# Schematic_Capstone.net
KiCad netlist of a schematic drawn in Altium Designer
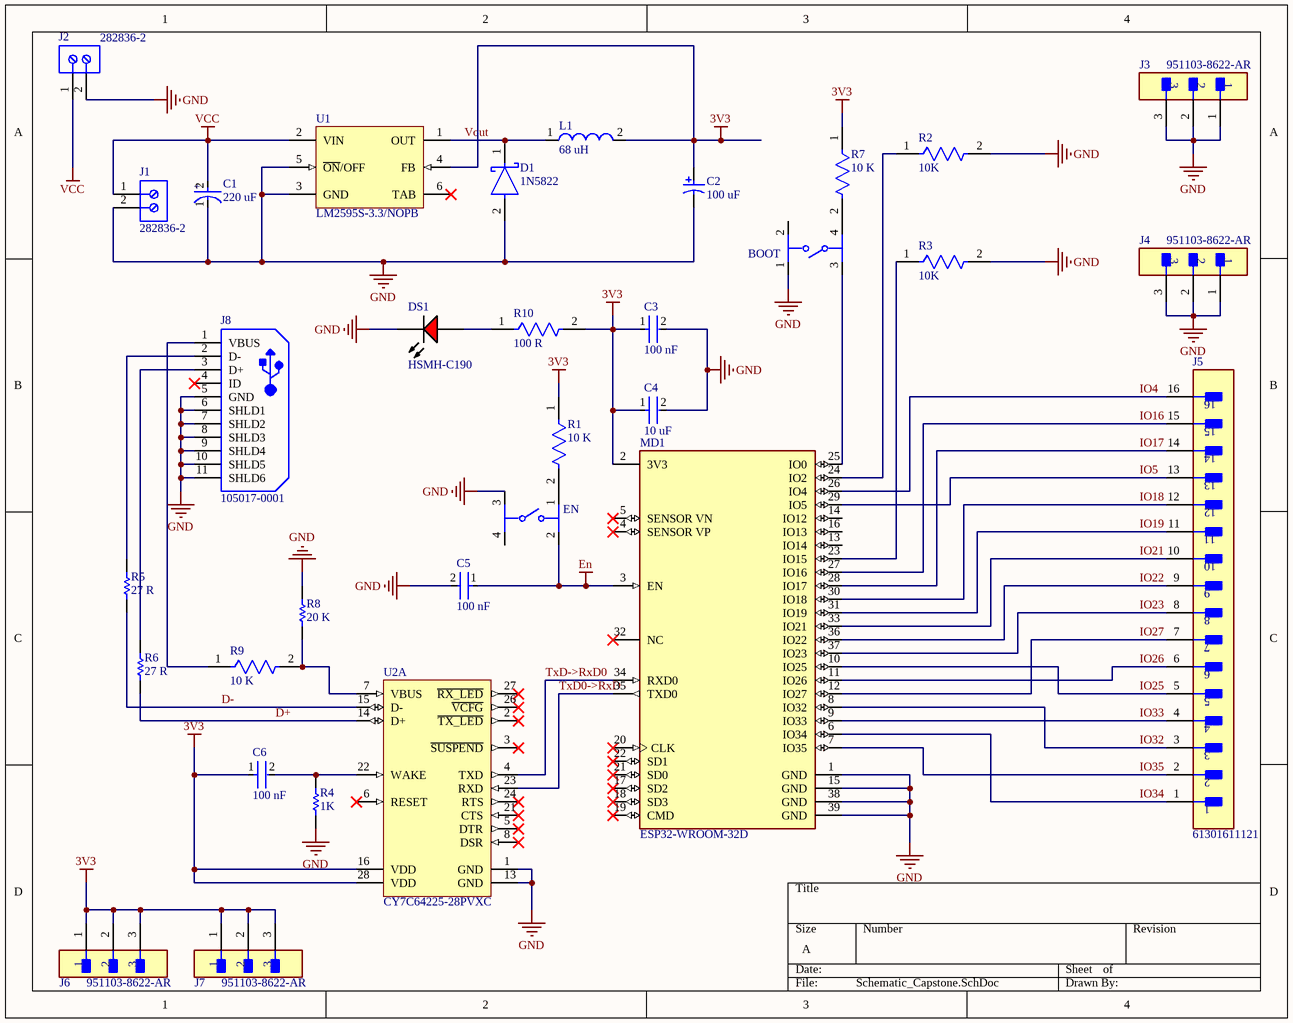
[diagram p0: Schematic_Capstone.SchDoc]

(export (version "E")
  (design (tool "Eeschema 10.0.6"))
  (components
    (comp (ref "BOOT")
      (value "PTS645SM43SMTR92LFS")
      (footprint "FP-PTS645SM43SMTR92LFS-MFG")
      (description "SWITCH TACTILE SPST-NO 0.05A 12V")
      (libsource (lib "Altium Content Vault") (part "1adf0dd01260c80cf25a44bfd6b99ba"))
    )
    (comp (ref "C1")
      (value "220 uF")
      (footprint "FP-860010473011-MFG")
      (description "CAP 220 UF 20% 25 V")
      (fields (field (name "TOLERANCE") "20%"))
      (libsource (lib "Altium Content Vault") (part "cf48714ba7e38822c1575c7ec0b6d1f"))
    )
    (comp (ref "C2")
      (value "100 uF")
      (footprint "VISH-7343-31_N")
      (fields (field (name "TOLERANCE") "1%"))
      (libsource (lib "Altium Content Vault") (part "CAP-P-2"))
    )
    (comp (ref "C3")
      (value "100 nF")
      (footprint "FP-C0805C-DN-MFG")
      (description "CAP CER 0.1UF 50V X7R 0805")
      (fields
        (field (name "MANUFACTURER PART NUMBER") "C0805C104K5RACTU")
        (field (name "MANUFACTURER") "KEMET")
      )
      (libsource (lib "Altium Content Vault") (part "b4654b650e69147ec39a6b967a45e02"))
    )
    (comp (ref "C4")
      (value "10 uF")
      (footprint "FP-C3225-250-0_45-MFG")
      (description "COMMERCIAL GRADE GENERAL PURPOSE")
      (libsource (lib "Altium Content Vault") (part "b4654b650e69147ec39a6b967a45e02"))
    )
    (comp (ref "C5")
      (value "100 nF")
      (footprint "FP-C0805C-DN-MFG")
      (description "CAP CER 0.1UF 50V X7R 0805")
      (fields
        (field (name "MANUFACTURER PART NUMBER") "C0805C104K5RACTU")
        (field (name "MANUFACTURER") "KEMET")
      )
      (libsource (lib "Altium Content Vault") (part "b4654b650e69147ec39a6b967a45e02"))
    )
    (comp (ref "C6")
      (value "100 nF")
      (footprint "FP-C0805C-DN-MFG")
      (description "CAP CER 0.1UF 50V X7R 0805")
      (fields
        (field (name "MANUFACTURER PART NUMBER") "C0805C104K5RACTU")
        (field (name "MANUFACTURER") "KEMET")
      )
      (libsource (lib "Altium Content Vault") (part "b4654b650e69147ec39a6b967a45e02"))
    )
    (comp (ref "D1")
      (value "1N5822")
      (footprint "FP-DO-201AD-MFG")
      (description "DIODE SCHOTTKY 40V 3A DO201AD")
      (fields
        (field (name "OCTOPART") "https://octopart.com/1n5822-stmicroelectronics-323225")
        (field (name "MANUFACTURER") "STMicroelectronics")
      )
      (libsource (lib "Altium Content Vault") (part "1d6ec82d83fb6aee721767c19dac4b9"))
    )
    (comp (ref "DS1")
      (value "HSMH-C190")
      (footprint "AVAG-HSMX-C190_V")
      (description "LED Uni-Color Red, 65 mW, 20 mA, -40 to 85 degC, 2-Pin SMD, RoHS, Tape and Reel")
      (libsource (lib "Altium Content Vault") (part "LED-RED-AK-2"))
    )
    (comp (ref "EN")
      (value "PTS645SM43SMTR92LFS")
      (footprint "FP-PTS645SM43SMTR92LFS-MFG")
      (description "SWITCH TACTILE SPST-NO 0.05A 12V")
      (libsource (lib "Altium Content Vault") (part "1adf0dd01260c80cf25a44bfd6b99ba"))
    )
    (comp (ref "J1")
      (value "282836-2")
      (footprint "TECO-282836-2_V")
      (description "Female Header, Pitch 5 mm, 1 x 2 Position, Height 10 mm, Tail Length 3.5 mm, Rohs, Bulk")
      (fields (field (name "VOLTAGE") "300V") (field (name "MANUFACTURER") "TE Connectivity"))
      (libsource (lib "Altium Content Vault") (part "CN-1P-F-TB2"))
    )
    (comp (ref "J2")
      (value "282836-2")
      (footprint "TECO-282836-2_V")
      (description "Female Header, Pitch 5 mm, 1 x 2 Position, Height 10 mm, Tail Length 3.5 mm, Rohs, Bulk")
      (fields (field (name "VOLTAGE") "300V") (field (name "MANUFACTURER") "TE Connectivity"))
      (libsource (lib "Altium Content Vault") (part "CN-1P-F-TB2"))
    )
    (comp (ref "J3")
      (value "951103-8622-AR")
      (footprint "FP-951103-8622-AR-MFG")
      (description "CONN HEADER VERT 3POS 2MM")
      (fields
        (field (name "OCTOPART") "https://octopart.com/951103-8622-ar-3m-14400669")
        (field (name "MANUFACTURER") "3M")
      )
      (libsource (lib "") (part "0d3f023dd272f625e17a2be33dea85f_1"))
    )
    (comp (ref "J4")
      (value "951103-8622-AR")
      (footprint "FP-951103-8622-AR-MFG")
      (description "CONN HEADER VERT 3POS 2MM")
      (fields
        (field (name "OCTOPART") "https://octopart.com/951103-8622-ar-3m-14400669")
        (field (name "MANUFACTURER") "3M")
      )
      (libsource (lib "") (part "0d3f023dd272f625e17a2be33dea85f_1"))
    )
    (comp (ref "J5")
      (value "61301611121")
      (footprint "FP-61301611121-MFG")
      (description "CONN HEADER VERT 16POS 2.54MM")
      (libsource (lib "Altium Content Vault") (part "e5c9d856941f54a8fdb498ab6b27a18"))
    )
    (comp (ref "J6")
      (value "951103-8622-AR")
      (footprint "FP-951103-8622-AR-MFG")
      (description "CONN HEADER VERT 3POS 2MM")
      (fields
        (field (name "OCTOPART") "https://octopart.com/951103-8622-ar-3m-14400669")
        (field (name "MANUFACTURER") "3M")
      )
      (libsource (lib "Altium Content Vault") (part "0d3f023dd272f625e17a2be33dea85f"))
    )
    (comp (ref "J7")
      (value "951103-8622-AR")
      (footprint "FP-951103-8622-AR-MFG")
      (description "CONN HEADER VERT 3POS 2MM")
      (fields
        (field (name "OCTOPART") "https://octopart.com/951103-8622-ar-3m-14400669")
        (field (name "MANUFACTURER") "3M")
      )
      (libsource (lib "Altium Content Vault") (part "0d3f023dd272f625e17a2be33dea85f"))
    )
    (comp (ref "J8")
      (value "105017-0001")
      (footprint "USB-MICRO-B_V")
      (fields (field (name "MANUFACTURER") "Molex"))
      (libsource (lib "Altium Content Vault") (part "USB-5-6SHLD"))
    )
    (comp (ref "L1")
      (value "68 uH")
      (footprint "WE-PD-L")
      (description "SMD-Shielded Power Inductor WE-PD, L = 68.0 µH")
      (libsource (lib "Altium Content Vault") (part "PAS-IND-INDUCTOR-2"))
    )
    (comp (ref "MD1")
      (value "ESP32-WROOM-32D")
      (footprint "FP-ESP32-WROOM-32D-MFG")
      (description "WIFI MODULE 32MBITS SPI FLASH")
      (fields
        (field (name "OCTOPART") "https://octopart.com/esp32-wroom-32d-espressif+systems-91040050")
        (field (name "MANUFACTURER") "Espressif Systems")
      )
      (libsource (lib "Altium Content Vault") (part "a031a76f8c27026a7a7f4657ff233a3"))
    )
    (comp (ref "R1")
      (value "10 K")
      (footprint "FP-CRCW2010-e3-IPC_B")
      (description "RES Thick Film, 10kΩ, 1%, 0.75W, 100ppm/°C, 2010")
      (fields (field (name "TOLERANCE") "1%"))
      (libsource (lib "Altium Content Vault") (part "1029c3af85768c4190bb7ad29bc67b5"))
    )
    (comp (ref "R2")
      (value "10K")
      (footprint "FP-CRCW2010-e3-IPC_B")
      (description "RES Thick Film, 10kΩ, 1%, 0.75W, 100ppm/°C, 2010")
      (fields (field (name "TOLERANCE") "1%"))
      (libsource (lib "Altium Content Vault") (part "1029c3af85768c4190bb7ad29bc67b5"))
    )
    (comp (ref "R3")
      (value "10K")
      (footprint "FP-CRCW2010-e3-IPC_B")
      (description "RES Thick Film, 10kΩ, 1%, 0.75W, 100ppm/°C, 2010")
      (fields (field (name "TOLERANCE") "1%"))
      (libsource (lib "Altium Content Vault") (part "1029c3af85768c4190bb7ad29bc67b5"))
    )
    (comp (ref "R4")
      (value "1K")
      (footprint "RESC1005X40X25NL05T05")
      (fields (field (name "MANUFACTURER") "Panasonic") (field (name "PART NUMBER") "ERJ-2GEJ102X"))
      (libsource (lib "Altium Content Vault") (part "RES"))
    )
    (comp (ref "R5")
      (value "27 R")
      (footprint "RESC3216X70X50NL05T20")
      (fields (field (name "MANUFACTURER") "Panasonic") (field (name "PART NUMBER") "ERJ8ENF27R0V"))
      (libsource (lib "Altium Content Vault") (part "RES"))
    )
    (comp (ref "R6")
      (value "27 R")
      (footprint "RESC3216X70X50NL05T20")
      (fields (field (name "MANUFACTURER") "Panasonic") (field (name "PART NUMBER") "ERJ8ENF27R0V"))
      (libsource (lib "Altium Content Vault") (part "RES"))
    )
    (comp (ref "R7")
      (value "10 K")
      (footprint "FP-CRCW2010-e3-IPC_B")
      (description "RES Thick Film, 10kΩ, 1%, 0.75W, 100ppm/°C, 2010")
      (fields (field (name "TOLERANCE") "1%"))
      (libsource (lib "Altium Content Vault") (part "1029c3af85768c4190bb7ad29bc67b5"))
    )
    (comp (ref "R8")
      (value "20 K")
      (footprint "RESC1608X55X25ML10T15")
      (fields (field (name "PART NUMBER") "RC0603FR-1020KL") (field (name "MANUFACTURER") "Yageo"))
      (libsource (lib "Altium Content Vault") (part "RES"))
    )
    (comp (ref "R9")
      (value "10 K")
      (footprint "FP-CRCW2010-e3-IPC_B")
      (description "RES Thick Film, 10kΩ, 1%, 0.75W, 100ppm/°C, 2010")
      (fields (field (name "TOLERANCE") "1%"))
      (libsource (lib "Altium Content Vault") (part "1029c3af85768c4190bb7ad29bc67b5"))
    )
    (comp (ref "R10")
      (value "100 R")
      (footprint "FP-CRCW0402-e3-IPC_C")
      (description "RES Thick Film, 100Ω, 1%, 0.063W, 100ppm/°C, 0402")
      (fields (field (name "TOLERANCE") "1%"))
      (libsource (lib "Altium Content Vault") (part "1029c3af85768c4190bb7ad29bc67b5"))
    )
    (comp (ref "U1")
      (value "LM2595S-3.3/NOPB")
      (footprint "KTT0005B_N")
      (description "SIMPLE SWITCHER® Power Converter 150 KHz 1A Step-Down Voltage Regulator, 5-pin TO-263, Pb-Free")
      (fields (field (name "MANUFACTURER") "Texas Instruments"))
      (libsource (lib "Altium Content Vault") (part "PM-REG-LM2595S-12"))
    )
    (comp (ref "U2")
      (value "CY7C64225-28PVXC")
      (footprint "CYP-PVX28_L")
      (description "USB-to-UART Bridge Controller, 3 to 5.25 V, 0 to 70 degC, 28-Pin SSOP (PVX28), Tube")
      (fields (field (name "MANUFACTURER") "Cypress"))
      (libsource (lib "Altium Content Vault") (part "CYP-CY7C6422-PV28"))
    )
  )
  (nets
    (net (code "1") (name "/D+") (class "Default")
      (node (ref "R6") (pin "1") (pinfunction "1_1") (pintype "passive"))
      (node (ref "U2") (pin "14") (pinfunction "D+_14") (pintype "bidirectional"))
    )
    (net (code "2") (name "/D-") (class "Default")
      (node (ref "R5") (pin "2") (pinfunction "2_2") (pintype "passive"))
      (node (ref "U2") (pin "15") (pinfunction "D-_15") (pintype "bidirectional"))
    )
    (net (code "3") (name "/IO4") (class "Default")
      (node (ref "J5") (pin "16") (pinfunction "16_16") (pintype "passive"))
      (node (ref "MD1") (pin "26") (pinfunction "IO4_26") (pintype "bidirectional"))
    )
    (net (code "4") (name "/IO5") (class "Default")
      (node (ref "J5") (pin "13") (pinfunction "13_13") (pintype "passive"))
      (node (ref "MD1") (pin "29") (pinfunction "IO5_29") (pintype "bidirectional"))
    )
    (net (code "5") (name "/IO16") (class "Default")
      (node (ref "J5") (pin "15") (pinfunction "15_15") (pintype "passive"))
      (node (ref "MD1") (pin "27") (pinfunction "IO16_27") (pintype "bidirectional"))
    )
    (net (code "6") (name "/IO17") (class "Default")
      (node (ref "J5") (pin "14") (pinfunction "14_14") (pintype "passive"))
      (node (ref "MD1") (pin "28") (pinfunction "IO17_28") (pintype "bidirectional"))
    )
    (net (code "7") (name "/IO18") (class "Default")
      (node (ref "J5") (pin "12") (pinfunction "12_12") (pintype "passive"))
      (node (ref "MD1") (pin "30") (pinfunction "IO18_30") (pintype "bidirectional"))
    )
    (net (code "8") (name "/IO19") (class "Default")
      (node (ref "J5") (pin "11") (pinfunction "11_11") (pintype "passive"))
      (node (ref "MD1") (pin "31") (pinfunction "IO19_31") (pintype "bidirectional"))
    )
    (net (code "9") (name "/IO21") (class "Default")
      (node (ref "J5") (pin "10") (pinfunction "10_10") (pintype "passive"))
      (node (ref "MD1") (pin "33") (pinfunction "IO21_33") (pintype "bidirectional"))
    )
    (net (code "10") (name "/IO22") (class "Default")
      (node (ref "J5") (pin "9") (pinfunction "9_9") (pintype "passive"))
      (node (ref "MD1") (pin "36") (pinfunction "IO22_36") (pintype "bidirectional"))
    )
    (net (code "11") (name "/IO23") (class "Default")
      (node (ref "J5") (pin "8") (pinfunction "8_8") (pintype "passive"))
      (node (ref "MD1") (pin "37") (pinfunction "IO23_37") (pintype "bidirectional"))
    )
    (net (code "12") (name "/IO25") (class "Default")
      (node (ref "J5") (pin "5") (pinfunction "5_5") (pintype "passive"))
      (node (ref "MD1") (pin "10") (pinfunction "IO25_10") (pintype "bidirectional"))
    )
    (net (code "13") (name "/IO26") (class "Default")
      (node (ref "J5") (pin "6") (pinfunction "6_6") (pintype "passive"))
      (node (ref "MD1") (pin "11") (pinfunction "IO26_11") (pintype "bidirectional"))
    )
    (net (code "14") (name "/IO27") (class "Default")
      (node (ref "J5") (pin "7") (pinfunction "7_7") (pintype "passive"))
      (node (ref "MD1") (pin "12") (pinfunction "IO27_12") (pintype "bidirectional"))
    )
    (net (code "15") (name "/IO32") (class "Default")
      (node (ref "J5") (pin "3") (pinfunction "3_3") (pintype "passive"))
      (node (ref "MD1") (pin "8") (pinfunction "IO32_8") (pintype "bidirectional"))
    )
    (net (code "16") (name "/IO33") (class "Default")
      (node (ref "J5") (pin "4") (pinfunction "4_4") (pintype "passive"))
      (node (ref "MD1") (pin "9") (pinfunction "IO33_9") (pintype "bidirectional"))
    )
    (net (code "17") (name "/IO34") (class "Default")
      (node (ref "J5") (pin "1") (pinfunction "1_1") (pintype "passive"))
      (node (ref "MD1") (pin "6") (pinfunction "IO34_6") (pintype "bidirectional"))
    )
    (net (code "18") (name "/IO35") (class "Default")
      (node (ref "J5") (pin "2") (pinfunction "2_2") (pintype "passive"))
      (node (ref "MD1") (pin "7") (pinfunction "IO35_7") (pintype "bidirectional"))
    )
    (net (code "19") (name "/TxD->RxD0") (class "Default")
      (node (ref "MD1") (pin "34") (pinfunction "RXD0_34") (pintype "input"))
      (node (ref "U2") (pin "4") (pinfunction "TXD_4") (pintype "output"))
    )
    (net (code "20") (name "/TxD0->RxD") (class "Default")
      (node (ref "MD1") (pin "35") (pinfunction "TXD0_35") (pintype "output"))
      (node (ref "U2") (pin "23") (pinfunction "RXD_23") (pintype "input"))
    )
    (net (code "21") (name "/Vout") (class "Default")
      (node (ref "D1") (pin "1") (pinfunction "C_1") (pintype "passive"))
      (node (ref "L1") (pin "1") (pinfunction "1_1") (pintype "passive"))
      (node (ref "U1") (pin "1") (pinfunction "OUT_1") (pintype "power_in"))
    )
    (net (code "22") (name "3V3") (class "Default")
      (node (ref "C2") (pin "1") (pinfunction "1_1") (pintype "passive"))
      (node (ref "C3") (pin "1") (pinfunction "1_1") (pintype "passive"))
      (node (ref "C4") (pin "1") (pinfunction "1_1") (pintype "passive"))
      (node (ref "C6") (pin "1") (pinfunction "1_1") (pintype "passive"))
      (node (ref "J6") (pin "1") (pinfunction "1_1") (pintype "passive"))
      (node (ref "J6") (pin "2") (pinfunction "2_2") (pintype "passive"))
      (node (ref "J6") (pin "3") (pinfunction "3_3") (pintype "passive"))
      (node (ref "J7") (pin "1") (pinfunction "1_1") (pintype "passive"))
      (node (ref "J7") (pin "2") (pinfunction "2_2") (pintype "passive"))
      (node (ref "J7") (pin "3") (pinfunction "3_3") (pintype "passive"))
      (node (ref "L1") (pin "2") (pinfunction "2_2") (pintype "passive"))
      (node (ref "MD1") (pin "2") (pinfunction "3V3_2") (pintype "power_in"))
      (node (ref "R1") (pin "1") (pinfunction "1_1") (pintype "passive"))
      (node (ref "R10") (pin "2") (pinfunction "2_2") (pintype "passive"))
      (node (ref "R7") (pin "1") (pinfunction "1_1") (pintype "passive"))
      (node (ref "U1") (pin "4") (pinfunction "FB_4") (pintype "input"))
      (node (ref "U2") (pin "16") (pinfunction "VDD_16") (pintype "power_in"))
      (node (ref "U2") (pin "28") (pinfunction "VDD_28") (pintype "power_in"))
    )
    (net (code "23") (name "En") (class "Default")
      (node (ref "C5") (pin "1") (pinfunction "1_1") (pintype "passive"))
      (node (ref "EN") (pin "2") (pinfunction "2_2") (pintype "passive"))
      (node (ref "MD1") (pin "3") (pinfunction "EN_3") (pintype "input"))
    )
    (net (code "24") (name "GND") (class "Default")
      (node (ref "BOOT") (pin "1") (pinfunction "1_1") (pintype "passive"))
      (node (ref "C1") (pin "1") (pinfunction "C_1") (pintype "passive"))
      (node (ref "C2") (pin "2") (pinfunction "2_2") (pintype "passive"))
      (node (ref "C3") (pin "2") (pinfunction "2_2") (pintype "passive"))
      (node (ref "C4") (pin "2") (pinfunction "2_2") (pintype "passive"))
      (node (ref "C5") (pin "2") (pinfunction "2_2") (pintype "passive"))
      (node (ref "D1") (pin "2") (pinfunction "A_2") (pintype "passive"))
      (node (ref "DS1") (pin "2") (pinfunction "K_2") (pintype "passive"))
      (node (ref "EN") (pin "3") (pinfunction "3_3") (pintype "passive"))
      (node (ref "J1") (pin "2") (pinfunction "2_2") (pintype "passive"))
      (node (ref "J2") (pin "2") (pinfunction "2_2") (pintype "passive"))
      (node (ref "J3") (pin "1") (pinfunction "1_1") (pintype "passive"))
      (node (ref "J3") (pin "2") (pinfunction "2_2") (pintype "passive"))
      (node (ref "J3") (pin "3") (pinfunction "3_3") (pintype "passive"))
      (node (ref "J4") (pin "1") (pinfunction "1_1") (pintype "passive"))
      (node (ref "J4") (pin "2") (pinfunction "2_2") (pintype "passive"))
      (node (ref "J4") (pin "3") (pinfunction "3_3") (pintype "passive"))
      (node (ref "J8") (pin "10") (pinfunction "SHLD5_10") (pintype "passive"))
      (node (ref "J8") (pin "11") (pinfunction "SHLD6_11") (pintype "passive"))
      (node (ref "J8") (pin "5") (pinfunction "GND_5") (pintype "passive"))
      (node (ref "J8") (pin "6") (pinfunction "SHLD1_6") (pintype "passive"))
      (node (ref "J8") (pin "7") (pinfunction "SHLD2_7") (pintype "passive"))
      (node (ref "J8") (pin "8") (pinfunction "SHLD3_8") (pintype "passive"))
      (node (ref "J8") (pin "9") (pinfunction "SHLD4_9") (pintype "passive"))
      (node (ref "MD1") (pin "1") (pinfunction "GND_1") (pintype "power_in"))
      (node (ref "MD1") (pin "15") (pinfunction "GND_15") (pintype "power_in"))
      (node (ref "MD1") (pin "38") (pinfunction "GND_38") (pintype "power_in"))
      (node (ref "MD1") (pin "39") (pinfunction "GND_39") (pintype "power_in"))
      (node (ref "R2") (pin "2") (pinfunction "2_2") (pintype "passive"))
      (node (ref "R3") (pin "2") (pinfunction "2_2") (pintype "passive"))
      (node (ref "R4") (pin "2") (pinfunction "2_2") (pintype "passive"))
      (node (ref "R8") (pin "2") (pinfunction "2_2") (pintype "passive"))
      (node (ref "U1") (pin "3") (pinfunction "GND_3") (pintype "power_in"))
      (node (ref "U1") (pin "5") (pinfunction "~{ON}/OFF_5") (pintype "input"))
      (node (ref "U2") (pin "1") (pinfunction "GND_1") (pintype "power_in"))
      (node (ref "U2") (pin "13") (pinfunction "GND_13") (pintype "power_in"))
    )
    (net (code "25") (name "Net-(BOOT-Pad4)") (class "Default")
      (node (ref "BOOT") (pin "4") (pinfunction "4_4") (pintype "passive"))
      (node (ref "R7") (pin "2") (pinfunction "2_2") (pintype "passive"))
    )
    (net (code "26") (name "Net-(DS1-A)") (class "Default")
      (node (ref "DS1") (pin "1") (pinfunction "A_1") (pintype "passive"))
      (node (ref "R10") (pin "1") (pinfunction "1_1") (pintype "passive"))
    )
    (net (code "27") (name "Net-(EN-Pad1)") (class "Default")
      (node (ref "EN") (pin "1") (pinfunction "1_1") (pintype "passive"))
      (node (ref "R1") (pin "2") (pinfunction "2_2") (pintype "passive"))
    )
    (net (code "28") (name "Net-(J8-D+)") (class "Default")
      (node (ref "J8") (pin "3") (pinfunction "D+_3") (pintype "passive"))
      (node (ref "R6") (pin "2") (pinfunction "2_2") (pintype "passive"))
    )
    (net (code "29") (name "Net-(J8-D-)") (class "Default")
      (node (ref "J8") (pin "2") (pinfunction "D-_2") (pintype "passive"))
      (node (ref "R5") (pin "1") (pinfunction "1_1") (pintype "passive"))
    )
    (net (code "30") (name "Net-(J8-VBUS)") (class "Default")
      (node (ref "J8") (pin "1") (pinfunction "VBUS_1") (pintype "passive"))
      (node (ref "R9") (pin "1") (pinfunction "1_1") (pintype "passive"))
    )
    (net (code "31") (name "Net-(MD1-IO0)") (class "Default")
      (node (ref "BOOT") (pin "3") (pinfunction "3_3") (pintype "passive"))
      (node (ref "MD1") (pin "25") (pinfunction "IO0_25") (pintype "bidirectional"))
    )
    (net (code "32") (name "Net-(MD1-IO2)") (class "Default")
      (node (ref "MD1") (pin "24") (pinfunction "IO2_24") (pintype "bidirectional"))
      (node (ref "R2") (pin "1") (pinfunction "1_1") (pintype "passive"))
    )
    (net (code "33") (name "Net-(MD1-IO15)") (class "Default")
      (node (ref "MD1") (pin "23") (pinfunction "IO15_23") (pintype "bidirectional"))
      (node (ref "R3") (pin "1") (pinfunction "1_1") (pintype "passive"))
    )
    (net (code "34") (name "Net-(U2A-VBUS)") (class "Default")
      (node (ref "R8") (pin "1") (pinfunction "1_1") (pintype "passive"))
      (node (ref "R9") (pin "2") (pinfunction "2_2") (pintype "passive"))
      (node (ref "U2") (pin "7") (pinfunction "VBUS_7") (pintype "input"))
    )
    (net (code "35") (name "Net-(U2A-WAKE)") (class "Default")
      (node (ref "C6") (pin "2") (pinfunction "2_2") (pintype "passive"))
      (node (ref "R4") (pin "1") (pinfunction "1_1") (pintype "passive"))
      (node (ref "U2") (pin "22") (pinfunction "WAKE_22") (pintype "input"))
    )
    (net (code "36") (name "VCC") (class "Default")
      (node (ref "C1") (pin "2") (pinfunction "A_2") (pintype "passive"))
      (node (ref "J1") (pin "1") (pinfunction "1_1") (pintype "passive"))
      (node (ref "J2") (pin "1") (pinfunction "1_1") (pintype "passive"))
      (node (ref "U1") (pin "2") (pinfunction "VIN_2") (pintype "power_in"))
    )
    (net (code "37") (name "unconnected-(BOOT-Pad2)") (class "Default")
      (node (ref "BOOT") (pin "2") (pinfunction "2_2") (pintype "passive"))
    )
    (net (code "38") (name "unconnected-(EN-Pad4)") (class "Default")
      (node (ref "EN") (pin "4") (pinfunction "4_4") (pintype "passive"))
    )
    (net (code "39") (name "unconnected-(J8-ID-Pad4)") (class "Default")
      (node (ref "J8") (pin "4") (pinfunction "ID_4") (pintype "passive+no_connect"))
    )
    (net (code "40") (name "unconnected-(MD1-CLK-Pad20)") (class "Default")
      (node (ref "MD1") (pin "20") (pinfunction "CLK_20") (pintype "input+no_connect"))
    )
    (net (code "41") (name "unconnected-(MD1-CMD-Pad19)") (class "Default")
      (node (ref "MD1") (pin "19") (pinfunction "CMD_19") (pintype "bidirectional+no_connect"))
    )
    (net (code "42") (name "unconnected-(MD1-IO12-Pad14)") (class "Default")
      (node (ref "MD1") (pin "14") (pinfunction "IO12_14") (pintype "bidirectional"))
    )
    (net (code "43") (name "unconnected-(MD1-IO13-Pad16)") (class "Default")
      (node (ref "MD1") (pin "16") (pinfunction "IO13_16") (pintype "bidirectional"))
    )
    (net (code "44") (name "unconnected-(MD1-IO14-Pad13)") (class "Default")
      (node (ref "MD1") (pin "13") (pinfunction "IO14_13") (pintype "bidirectional"))
    )
    (net (code "45") (name "unconnected-(MD1-NC-Pad32)") (class "Default")
      (node (ref "MD1") (pin "32") (pinfunction "NC_32") (pintype "passive+no_connect"))
    )
    (net (code "46") (name "unconnected-(MD1-SD0-Pad21)") (class "Default")
      (node (ref "MD1") (pin "21") (pinfunction "SD0_21") (pintype "bidirectional+no_connect"))
    )
    (net (code "47") (name "unconnected-(MD1-SD1-Pad22)") (class "Default")
      (node (ref "MD1") (pin "22") (pinfunction "SD1_22") (pintype "bidirectional+no_connect"))
    )
    (net (code "48") (name "unconnected-(MD1-SD2-Pad17)") (class "Default")
      (node (ref "MD1") (pin "17") (pinfunction "SD2_17") (pintype "bidirectional+no_connect"))
    )
    (net (code "49") (name "unconnected-(MD1-SD3-Pad18)") (class "Default")
      (node (ref "MD1") (pin "18") (pinfunction "SD3_18") (pintype "bidirectional+no_connect"))
    )
    (net (code "50") (name "unconnected-(MD1-SENSOR_VN-Pad5)") (class "Default")
      (node (ref "MD1") (pin "5") (pinfunction "SENSOR_VN_5") (pintype "bidirectional+no_connect"))
    )
    (net (code "51") (name "unconnected-(MD1-SENSOR_VP-Pad4)") (class "Default")
      (node (ref "MD1") (pin "4") (pinfunction "SENSOR_VP_4") (pintype "bidirectional+no_connect"))
    )
    (net (code "52") (name "unconnected-(U1-TAB-Pad6)") (class "Default")
      (node (ref "U1") (pin "6") (pinfunction "TAB_6") (pintype "power_in+no_connect"))
    )
    (net (code "53") (name "unconnected-(U2A-CTS-Pad21)") (class "Default")
      (node (ref "U2") (pin "21") (pinfunction "CTS_21") (pintype "input+no_connect"))
    )
    (net (code "54") (name "unconnected-(U2A-DSR-Pad8)") (class "Default")
      (node (ref "U2") (pin "8") (pinfunction "DSR_8") (pintype "input+no_connect"))
    )
    (net (code "55") (name "unconnected-(U2A-DTR-Pad5)") (class "Default")
      (node (ref "U2") (pin "5") (pinfunction "DTR_5") (pintype "output+no_connect"))
    )
    (net (code "56") (name "unconnected-(U2A-RESET-Pad6)") (class "Default")
      (node (ref "U2") (pin "6") (pinfunction "RESET_6") (pintype "input+no_connect"))
    )
    (net (code "57") (name "unconnected-(U2A-RTS-Pad24)") (class "Default")
      (node (ref "U2") (pin "24") (pinfunction "RTS_24") (pintype "output+no_connect"))
    )
    (net (code "58") (name "unconnected-(U2A-~{RX_LED}-Pad27)") (class "Default")
      (node (ref "U2") (pin "27") (pinfunction "~{RX_LED}_27") (pintype "output+no_connect"))
    )
    (net (code "59") (name "unconnected-(U2A-~{SUSPEND}-Pad3)") (class "Default")
      (node (ref "U2") (pin "3") (pinfunction "~{SUSPEND}_3") (pintype "output+no_connect"))
    )
    (net (code "60") (name "unconnected-(U2A-~{TX_LED}-Pad2)") (class "Default")
      (node (ref "U2") (pin "2") (pinfunction "~{TX_LED}_2") (pintype "output+no_connect"))
    )
    (net (code "61") (name "unconnected-(U2A-~{VCFG}-Pad26)") (class "Default")
      (node (ref "U2") (pin "26") (pinfunction "~{VCFG}_26") (pintype "output+no_connect"))
    )
  )
)
